# design.net
KiCad netlist of a schematic drawn in Altium Designer
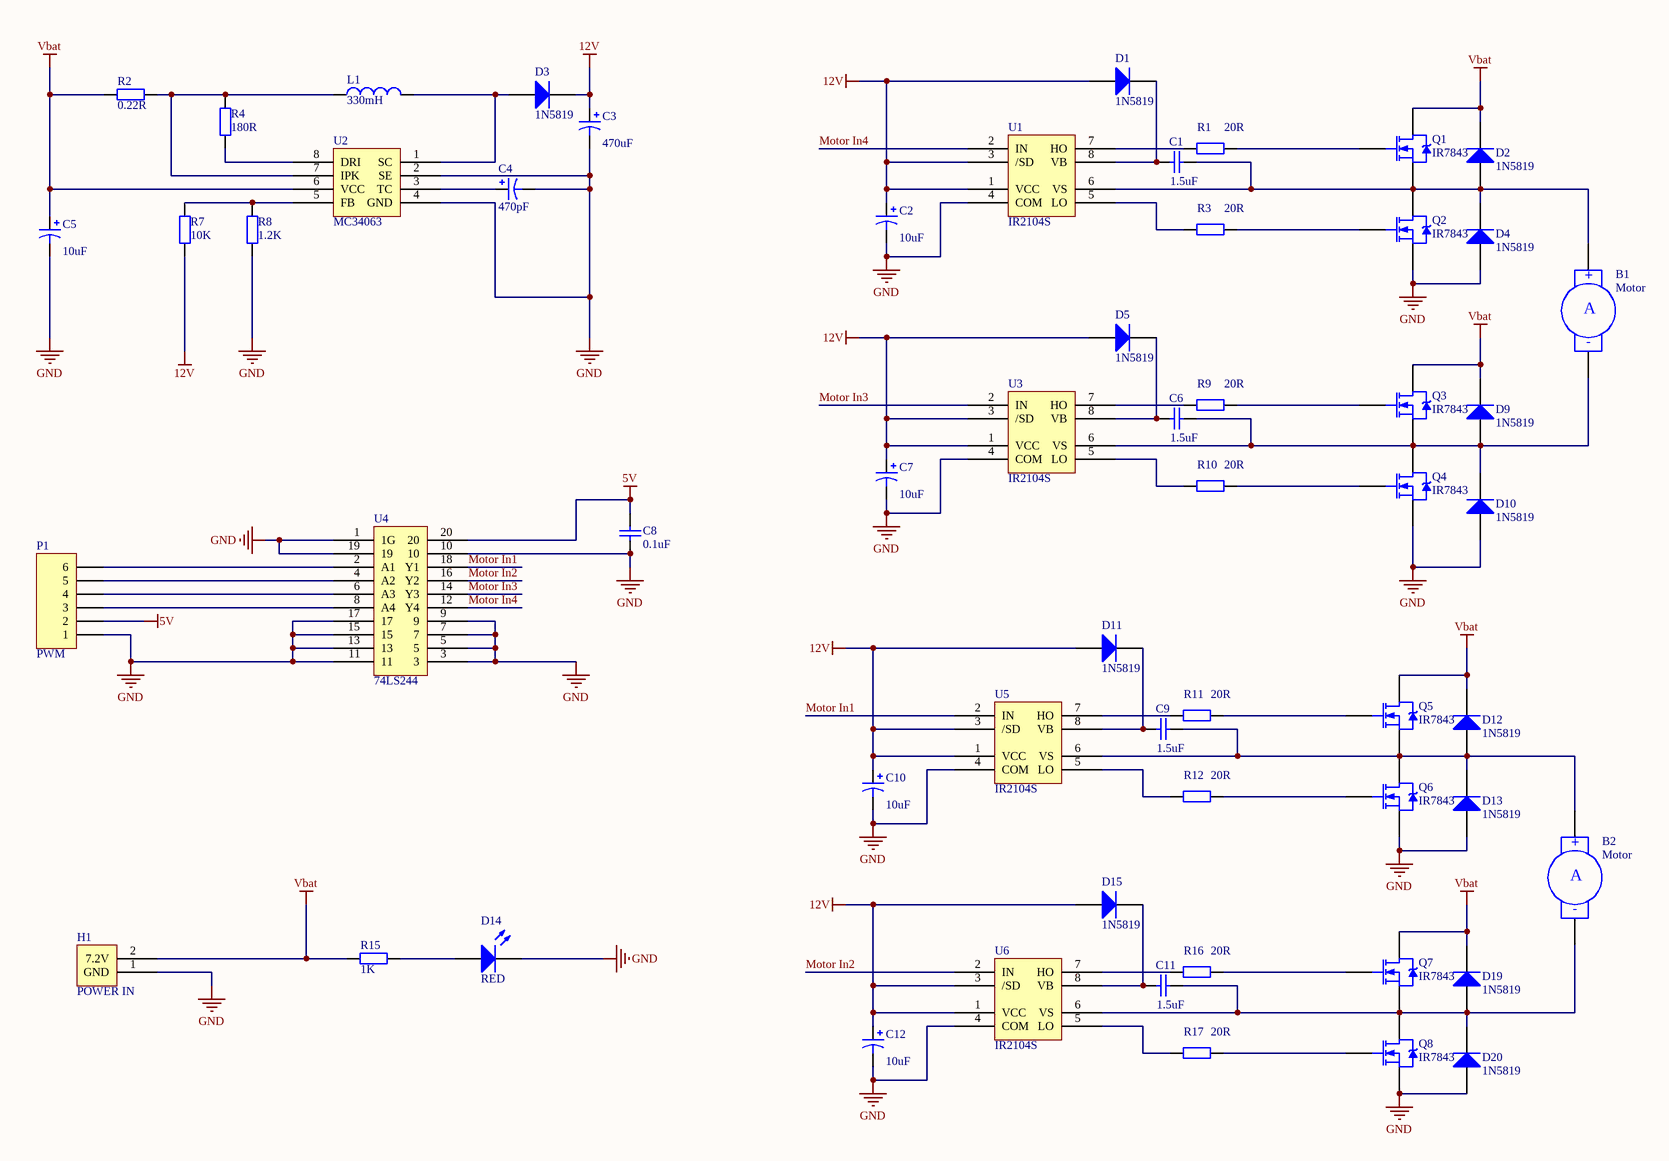
[diagram p0: 驱动原理图.SchDoc]

(export (version "E")
  (design (tool "Eeschema 10.0.6"))
  (components
    (comp (ref "B1")
      (value "Motor")
      (footprint "KF301-2P")
      (description "Servo Motor")
      (fields (field (name "PUBLISHER") "Altium Limited"))
      (libsource (lib "Miscellaneous Devices") (part "Motor Servo"))
    )
    (comp (ref "B2")
      (value "Motor")
      (footprint "KF301-2P")
      (description "Servo Motor")
      (fields (field (name "PUBLISHER") "Altium Limited"))
      (libsource (lib "Miscellaneous Devices") (part "Motor Servo"))
    )
    (comp (ref "C1")
      (value "1.5uF")
      (footprint "0805(2012)")
      (description "Capacitor")
      (fields (field (name "Comment") "Cap") (field (name "PUBLISHER") "Altium Limited"))
      (libsource (lib "Miscellaneous Devices") (part "Cap"))
    )
    (comp (ref "C2")
      (value "10uF")
      (footprint "SOD-323(0805)")
      (description "Polarized Capacitor (Radial)")
      (fields (field (name "Comment") "Cap Pol1") (field (name "PUBLISHER") "Altium Limited"))
      (libsource (lib "Miscellaneous Devices") (part "Cap Pol1"))
    )
    (comp (ref "C3")
      (value "470uF")
      (footprint "RB5-10.5")
      (description "Polarized Capacitor (Radial)")
      (fields (field (name "Comment") "Cap Pol1") (field (name "PUBLISHER") "Altium Limited"))
      (libsource (lib "Miscellaneous Devices") (part "Cap Pol1"))
    )
    (comp (ref "C4")
      (value "470pF")
      (footprint "SOD-323(0805)")
      (description "Polarized Capacitor (Radial)")
      (fields (field (name "Comment") "Cap Pol1") (field (name "PUBLISHER") "Altium Limited"))
      (libsource (lib "Miscellaneous Devices") (part "Cap Pol1"))
    )
    (comp (ref "C5")
      (value "10uF")
      (footprint "SOD-323(0805)")
      (description "Polarized Capacitor (Radial)")
      (fields (field (name "Comment") "Cap Pol1") (field (name "PUBLISHER") "Altium Limited"))
      (libsource (lib "Miscellaneous Devices") (part "Cap Pol1"))
    )
    (comp (ref "C6")
      (value "1.5uF")
      (footprint "0805(2012)")
      (description "Capacitor")
      (fields (field (name "Comment") "Cap") (field (name "PUBLISHER") "Altium Limited"))
      (libsource (lib "Miscellaneous Devices") (part "Cap"))
    )
    (comp (ref "C7")
      (value "10uF")
      (footprint "SOD-323(0805)")
      (description "Polarized Capacitor (Radial)")
      (fields (field (name "Comment") "Cap Pol1") (field (name "PUBLISHER") "Altium Limited"))
      (libsource (lib "Miscellaneous Devices") (part "Cap Pol1"))
    )
    (comp (ref "C8")
      (value "0.1uF")
      (footprint "0805(2012)")
      (description "Capacitor")
      (fields (field (name "Comment") "Cap") (field (name "PUBLISHER") "Altium Limited"))
      (libsource (lib "LY") (part "Cap"))
    )
    (comp (ref "C9")
      (value "1.5uF")
      (footprint "0805(2012)")
      (description "Capacitor")
      (fields (field (name "Comment") "Cap") (field (name "PUBLISHER") "Altium Limited"))
      (libsource (lib "Miscellaneous Devices") (part "Cap"))
    )
    (comp (ref "C10")
      (value "10uF")
      (footprint "SOD-323(0805)")
      (description "Polarized Capacitor (Radial)")
      (fields (field (name "Comment") "Cap Pol1") (field (name "PUBLISHER") "Altium Limited"))
      (libsource (lib "Miscellaneous Devices") (part "Cap Pol1"))
    )
    (comp (ref "C11")
      (value "1.5uF")
      (footprint "0805(2012)")
      (description "Capacitor")
      (fields (field (name "Comment") "Cap") (field (name "PUBLISHER") "Altium Limited"))
      (libsource (lib "Miscellaneous Devices") (part "Cap"))
    )
    (comp (ref "C12")
      (value "10uF")
      (footprint "SOD-323(0805)")
      (description "Polarized Capacitor (Radial)")
      (fields (field (name "Comment") "Cap Pol1") (field (name "PUBLISHER") "Altium Limited"))
      (libsource (lib "Miscellaneous Devices") (part "Cap Pol1"))
    )
    (comp (ref "D1")
      (value "1N5819")
      (footprint "0805(2012)")
      (description "Silicon Epitaxial Planar Diode for Various Detector, Modulator, Demodulator")
      (fields (field (name "PUBLISHER") "Altium Limited"))
      (libsource (lib "Renesas Diode") (part "1N4148"))
    )
    (comp (ref "D2")
      (value "1N5819")
      (footprint "0805(2012)")
      (description "Silicon Epitaxial Planar Diode for Various Detector, Modulator, Demodulator")
      (fields (field (name "PUBLISHER") "Altium Limited"))
      (libsource (lib "Renesas Diode") (part "1N4148"))
    )
    (comp (ref "D3")
      (value "1N5819")
      (footprint "0805(2012)")
      (description "Silicon Epitaxial Planar Diode for Various Detector, Modulator, Demodulator")
      (fields (field (name "PUBLISHER") "Altium Limited"))
      (libsource (lib "Renesas Diode") (part "1N4148"))
    )
    (comp (ref "D4")
      (value "1N5819")
      (footprint "0805(2012)")
      (description "Silicon Epitaxial Planar Diode for Various Detector, Modulator, Demodulator")
      (fields (field (name "PUBLISHER") "Altium Limited"))
      (libsource (lib "Renesas Diode") (part "1N4148"))
    )
    (comp (ref "D5")
      (value "1N5819")
      (footprint "0805(2012)")
      (description "Silicon Epitaxial Planar Diode for Various Detector, Modulator, Demodulator")
      (fields (field (name "PUBLISHER") "Altium Limited"))
      (libsource (lib "Renesas Diode") (part "1N4148"))
    )
    (comp (ref "D9")
      (value "1N5819")
      (footprint "0805(2012)")
      (description "Silicon Epitaxial Planar Diode for Various Detector, Modulator, Demodulator")
      (fields (field (name "PUBLISHER") "Altium Limited"))
      (libsource (lib "Renesas Diode") (part "1N4148"))
    )
    (comp (ref "D10")
      (value "1N5819")
      (footprint "0805(2012)")
      (description "Silicon Epitaxial Planar Diode for Various Detector, Modulator, Demodulator")
      (fields (field (name "PUBLISHER") "Altium Limited"))
      (libsource (lib "Renesas Diode") (part "1N4148"))
    )
    (comp (ref "D11")
      (value "1N5819")
      (footprint "0805(2012)")
      (description "Silicon Epitaxial Planar Diode for Various Detector, Modulator, Demodulator")
      (fields (field (name "PUBLISHER") "Altium Limited"))
      (libsource (lib "Renesas Diode") (part "1N4148"))
    )
    (comp (ref "D12")
      (value "1N5819")
      (footprint "0805(2012)")
      (description "Silicon Epitaxial Planar Diode for Various Detector, Modulator, Demodulator")
      (fields (field (name "PUBLISHER") "Altium Limited"))
      (libsource (lib "Renesas Diode") (part "1N4148"))
    )
    (comp (ref "D13")
      (value "1N5819")
      (footprint "0805(2012)")
      (description "Silicon Epitaxial Planar Diode for Various Detector, Modulator, Demodulator")
      (fields (field (name "PUBLISHER") "Altium Limited"))
      (libsource (lib "Renesas Diode") (part "1N4148"))
    )
    (comp (ref "D14")
      (value "RED")
      (footprint "0805LED")
      (description "Typical RED, GREEN, YELLOW, AMBER GaAs LED")
      (fields (field (name "PUBLISHER") "Altium Limited"))
      (libsource (lib "LY") (part "LED2"))
    )
    (comp (ref "D15")
      (value "1N5819")
      (footprint "0805(2012)")
      (description "Silicon Epitaxial Planar Diode for Various Detector, Modulator, Demodulator")
      (fields (field (name "PUBLISHER") "Altium Limited"))
      (libsource (lib "Renesas Diode") (part "1N4148"))
    )
    (comp (ref "D19")
      (value "1N5819")
      (footprint "0805(2012)")
      (description "Silicon Epitaxial Planar Diode for Various Detector, Modulator, Demodulator")
      (fields (field (name "PUBLISHER") "Altium Limited"))
      (libsource (lib "Renesas Diode") (part "1N4148"))
    )
    (comp (ref "D20")
      (value "1N5819")
      (footprint "0805(2012)")
      (description "Silicon Epitaxial Planar Diode for Various Detector, Modulator, Demodulator")
      (fields (field (name "PUBLISHER") "Altium Limited"))
      (libsource (lib "Renesas Diode") (part "1N4148"))
    )
    (comp (ref "H1")
      (value "POWER IN")
      (footprint "KF301-2P")
      (libsource (lib "MOS motor") (part "POWER IN"))
    )
    (comp (ref "L1")
      (value "330mH")
      (footprint "电感10*12")
      (description "Inductor")
      (fields (field (name "PUBLISHER") "Altium Limited"))
      (libsource (lib "Miscellaneous Devices") (part "Inductor"))
    )
    (comp (ref "P1")
      (value "PWM")
      (footprint "HDR1X6")
      (description "Header, 6-Pin")
      (fields (field (name "PUBLISHER") "Altium Limited"))
      (libsource (lib "Miscellaneous Connectors") (part "Header 6"))
    )
    (comp (ref "Q1")
      (value "IR7843")
      (footprint "LR7843")
      (description "N-Channel Power MOSFET")
      (fields (field (name "PUBLISHER") "Altium Limited"))
      (libsource (lib "PowerIn") (part "IR7843"))
    )
    (comp (ref "Q2")
      (value "IR7843")
      (footprint "LR7843")
      (description "N-Channel Power MOSFET")
      (fields (field (name "PUBLISHER") "Altium Limited"))
      (libsource (lib "PowerIn") (part "IR7843"))
    )
    (comp (ref "Q3")
      (value "IR7843")
      (footprint "LR7843")
      (description "N-Channel Power MOSFET")
      (fields (field (name "PUBLISHER") "Altium Limited"))
      (libsource (lib "PowerIn") (part "IR7843"))
    )
    (comp (ref "Q4")
      (value "IR7843")
      (footprint "LR7843")
      (description "N-Channel Power MOSFET")
      (fields (field (name "PUBLISHER") "Altium Limited"))
      (libsource (lib "PowerIn") (part "IR7843"))
    )
    (comp (ref "Q5")
      (value "IR7843")
      (footprint "LR7843")
      (description "N-Channel Power MOSFET")
      (fields (field (name "PUBLISHER") "Altium Limited"))
      (libsource (lib "PowerIn") (part "IR7843"))
    )
    (comp (ref "Q6")
      (value "IR7843")
      (footprint "LR7843")
      (description "N-Channel Power MOSFET")
      (fields (field (name "PUBLISHER") "Altium Limited"))
      (libsource (lib "PowerIn") (part "IR7843"))
    )
    (comp (ref "Q7")
      (value "IR7843")
      (footprint "LR7843")
      (description "N-Channel Power MOSFET")
      (fields (field (name "PUBLISHER") "Altium Limited"))
      (libsource (lib "PowerIn") (part "IR7843"))
    )
    (comp (ref "Q8")
      (value "IR7843")
      (footprint "LR7843")
      (description "N-Channel Power MOSFET")
      (fields (field (name "PUBLISHER") "Altium Limited"))
      (libsource (lib "PowerIn") (part "IR7843"))
    )
    (comp (ref "R1")
      (value "20R")
      (footprint "0805(2012)")
      (description "Resistor")
      (fields (field (name "Comment") "Res2") (field (name "PUBLISHER") "Altium Limited"))
      (libsource (lib "altium-import") (part "root_0_Res2_"))
    )
    (comp (ref "R2")
      (value "0.22R")
      (footprint "1206(3216)")
      (description "Resistor")
      (fields (field (name "Comment") "Res2") (field (name "PUBLISHER") "Altium Limited"))
      (libsource (lib "altium-import") (part "root_2_Res2_"))
    )
    (comp (ref "R3")
      (value "20R")
      (footprint "0805(2012)")
      (description "Resistor")
      (fields (field (name "Comment") "Res2") (field (name "PUBLISHER") "Altium Limited"))
      (libsource (lib "altium-import") (part "root_0_Res2_"))
    )
    (comp (ref "R4")
      (value "180R")
      (footprint "0805(2012)")
      (description "Resistor")
      (fields (field (name "Comment") "Res2") (field (name "PUBLISHER") "Altium Limited"))
      (libsource (lib "LY") (part "Res2"))
    )
    (comp (ref "R7")
      (value "10K")
      (footprint "0805(2012)")
      (description "Resistor")
      (fields (field (name "Comment") "Res2") (field (name "PUBLISHER") "Altium Limited"))
      (libsource (lib "LY") (part "Res2"))
    )
    (comp (ref "R8")
      (value "1.2K")
      (footprint "0805(2012)")
      (description "Resistor")
      (fields (field (name "Comment") "Res2") (field (name "PUBLISHER") "Altium Limited"))
      (libsource (lib "LY") (part "Res2"))
    )
    (comp (ref "R9")
      (value "20R")
      (footprint "0805(2012)")
      (description "Resistor")
      (fields (field (name "Comment") "Res2") (field (name "PUBLISHER") "Altium Limited"))
      (libsource (lib "altium-import") (part "root_0_Res2_"))
    )
    (comp (ref "R10")
      (value "20R")
      (footprint "0805(2012)")
      (description "Resistor")
      (fields (field (name "Comment") "Res2") (field (name "PUBLISHER") "Altium Limited"))
      (libsource (lib "altium-import") (part "root_0_Res2_"))
    )
    (comp (ref "R11")
      (value "20R")
      (footprint "0805(2012)")
      (description "Resistor")
      (fields (field (name "Comment") "Res2") (field (name "PUBLISHER") "Altium Limited"))
      (libsource (lib "altium-import") (part "root_0_Res2_"))
    )
    (comp (ref "R12")
      (value "20R")
      (footprint "0805(2012)")
      (description "Resistor")
      (fields (field (name "Comment") "Res2") (field (name "PUBLISHER") "Altium Limited"))
      (libsource (lib "altium-import") (part "root_0_Res2_"))
    )
    (comp (ref "R15")
      (value "1K")
      (footprint "0805(2012)")
      (description "Resistor")
      (fields (field (name "Comment") "Res2") (field (name "PUBLISHER") "Altium Limited"))
      (libsource (lib "") (part "Res2_1"))
    )
    (comp (ref "R16")
      (value "20R")
      (footprint "0805(2012)")
      (description "Resistor")
      (fields (field (name "Comment") "Res2") (field (name "PUBLISHER") "Altium Limited"))
      (libsource (lib "altium-import") (part "root_0_Res2_"))
    )
    (comp (ref "R17")
      (value "20R")
      (footprint "0805(2012)")
      (description "Resistor")
      (fields (field (name "Comment") "Res2") (field (name "PUBLISHER") "Altium Limited"))
      (libsource (lib "altium-import") (part "root_0_Res2_"))
    )
    (comp (ref "U1") (value "IR2104S") (footprint "IR2104S") (libsource (lib "LY") (part "IR2104S")))
    (comp (ref "U2") (value "MC34063") (footprint "MC34063") (libsource (lib "LY") (part "MC34063")))
    (comp (ref "U3") (value "IR2104S") (footprint "IR2104S") (libsource (lib "LY") (part "IR2104S")))
    (comp (ref "U4") (value "74LS244") (footprint "74ls244DA") (libsource (lib "LY") (part "74LS244")))
    (comp (ref "U5") (value "IR2104S") (footprint "IR2104S") (libsource (lib "LY") (part "IR2104S")))
    (comp (ref "U6") (value "IR2104S") (footprint "IR2104S") (libsource (lib "LY") (part "IR2104S")))
  )
  (nets
    (net (code "1") (name "/Motor In1") (class "Default")
      (node (ref "U4") (pin "18") (pinfunction "Y1_18") (pintype "passive"))
      (node (ref "U5") (pin "2") (pinfunction "IN_2") (pintype "passive"))
    )
    (net (code "2") (name "/Motor In2") (class "Default")
      (node (ref "U4") (pin "16") (pinfunction "Y2_16") (pintype "passive"))
      (node (ref "U6") (pin "2") (pinfunction "IN_2") (pintype "passive"))
    )
    (net (code "3") (name "/Motor In3") (class "Default")
      (node (ref "U3") (pin "2") (pinfunction "IN_2") (pintype "passive"))
      (node (ref "U4") (pin "14") (pinfunction "Y3_14") (pintype "passive"))
    )
    (net (code "4") (name "/Motor In4") (class "Default")
      (node (ref "U1") (pin "2") (pinfunction "IN_2") (pintype "passive"))
      (node (ref "U4") (pin "12") (pinfunction "Y4_12") (pintype "passive"))
    )
    (net (code "5") (name "5V") (class "Default")
      (node (ref "C8") (pin "2") (pinfunction "2_2") (pintype "passive"))
      (node (ref "P1") (pin "2") (pinfunction "2_2") (pintype "passive"))
      (node (ref "U4") (pin "20") (pinfunction "20_20") (pintype "passive"))
    )
    (net (code "6") (name "12V") (class "Default")
      (node (ref "C10") (pin "1") (pinfunction "1_1") (pintype "passive"))
      (node (ref "C12") (pin "1") (pinfunction "1_1") (pintype "passive"))
      (node (ref "C2") (pin "1") (pinfunction "1_1") (pintype "passive"))
      (node (ref "C3") (pin "1") (pinfunction "1_1") (pintype "passive"))
      (node (ref "C7") (pin "1") (pinfunction "1_1") (pintype "passive"))
      (node (ref "D1") (pin "2") (pinfunction "A_2") (pintype "passive"))
      (node (ref "D11") (pin "2") (pinfunction "A_2") (pintype "passive"))
      (node (ref "D15") (pin "2") (pinfunction "A_2") (pintype "passive"))
      (node (ref "D3") (pin "1") (pinfunction "K_1") (pintype "passive"))
      (node (ref "D5") (pin "2") (pinfunction "A_2") (pintype "passive"))
      (node (ref "R7") (pin "1") (pinfunction "1_1") (pintype "passive"))
      (node (ref "U1") (pin "1") (pinfunction "VCC_1") (pintype "passive"))
      (node (ref "U1") (pin "3") (pinfunction "/SD_3") (pintype "passive"))
      (node (ref "U3") (pin "1") (pinfunction "VCC_1") (pintype "passive"))
      (node (ref "U3") (pin "3") (pinfunction "/SD_3") (pintype "passive"))
      (node (ref "U5") (pin "1") (pinfunction "VCC_1") (pintype "passive"))
      (node (ref "U5") (pin "3") (pinfunction "/SD_3") (pintype "passive"))
      (node (ref "U6") (pin "1") (pinfunction "VCC_1") (pintype "passive"))
      (node (ref "U6") (pin "3") (pinfunction "/SD_3") (pintype "passive"))
    )
    (net (code "7") (name "GND") (class "Default")
      (node (ref "C10") (pin "2") (pinfunction "2_2") (pintype "passive"))
      (node (ref "C12") (pin "2") (pinfunction "2_2") (pintype "passive"))
      (node (ref "C2") (pin "2") (pinfunction "2_2") (pintype "passive"))
      (node (ref "C3") (pin "2") (pinfunction "2_2") (pintype "passive"))
      (node (ref "C4") (pin "2") (pinfunction "2_2") (pintype "passive"))
      (node (ref "C5") (pin "2") (pinfunction "2_2") (pintype "passive"))
      (node (ref "C7") (pin "2") (pinfunction "2_2") (pintype "passive"))
      (node (ref "C8") (pin "1") (pinfunction "1_1") (pintype "passive"))
      (node (ref "D10") (pin "2") (pinfunction "A_2") (pintype "passive"))
      (node (ref "D13") (pin "2") (pinfunction "A_2") (pintype "passive"))
      (node (ref "D14") (pin "2") (pinfunction "K_2") (pintype "passive"))
      (node (ref "D20") (pin "2") (pinfunction "A_2") (pintype "passive"))
      (node (ref "D4") (pin "2") (pinfunction "A_2") (pintype "passive"))
      (node (ref "H1") (pin "1") (pinfunction "GND_1") (pintype "passive"))
      (node (ref "P1") (pin "1") (pinfunction "1_1") (pintype "passive"))
      (node (ref "Q2") (pin "3") (pinfunction "S_3") (pintype "passive"))
      (node (ref "Q4") (pin "3") (pinfunction "S_3") (pintype "passive"))
      (node (ref "Q6") (pin "3") (pinfunction "S_3") (pintype "passive"))
      (node (ref "Q8") (pin "3") (pinfunction "S_3") (pintype "passive"))
      (node (ref "R8") (pin "1") (pinfunction "1_1") (pintype "passive"))
      (node (ref "U1") (pin "4") (pinfunction "COM_4") (pintype "passive"))
      (node (ref "U2") (pin "2") (pinfunction "SE_2") (pintype "passive"))
      (node (ref "U2") (pin "4") (pinfunction "GND_4") (pintype "passive"))
      (node (ref "U3") (pin "4") (pinfunction "COM_4") (pintype "passive"))
      (node (ref "U4") (pin "1") (pinfunction "1G_1") (pintype "passive"))
      (node (ref "U4") (pin "10") (pinfunction "10_10") (pintype "passive"))
      (node (ref "U4") (pin "11") (pinfunction "11_11") (pintype "passive"))
      (node (ref "U4") (pin "13") (pinfunction "13_13") (pintype "passive"))
      (node (ref "U4") (pin "15") (pinfunction "15_15") (pintype "passive"))
      (node (ref "U4") (pin "17") (pinfunction "17_17") (pintype "passive"))
      (node (ref "U4") (pin "19") (pinfunction "19_19") (pintype "passive"))
      (node (ref "U4") (pin "3") (pinfunction "3_3") (pintype "passive"))
      (node (ref "U4") (pin "5") (pinfunction "5_5") (pintype "passive"))
      (node (ref "U4") (pin "7") (pinfunction "7_7") (pintype "passive"))
      (node (ref "U4") (pin "9") (pinfunction "9_9") (pintype "passive"))
      (node (ref "U5") (pin "4") (pinfunction "COM_4") (pintype "passive"))
      (node (ref "U6") (pin "4") (pinfunction "COM_4") (pintype "passive"))
    )
    (net (code "8") (name "Net-(B1-+)") (class "Default")
      (node (ref "B1") (pin "1") (pinfunction "+_1") (pintype "passive"))
      (node (ref "C1") (pin "2") (pinfunction "2_2") (pintype "passive"))
      (node (ref "D2") (pin "2") (pinfunction "A_2") (pintype "passive"))
      (node (ref "D4") (pin "1") (pinfunction "K_1") (pintype "passive"))
      (node (ref "Q1") (pin "3") (pinfunction "S_3") (pintype "passive"))
      (node (ref "Q2") (pin "2") (pinfunction "D_2") (pintype "passive"))
      (node (ref "U1") (pin "6") (pinfunction "VS_6") (pintype "passive"))
    )
    (net (code "9") (name "Net-(B1--)") (class "Default")
      (node (ref "B1") (pin "2") (pinfunction "-_2") (pintype "passive"))
      (node (ref "C6") (pin "2") (pinfunction "2_2") (pintype "passive"))
      (node (ref "D10") (pin "1") (pinfunction "K_1") (pintype "passive"))
      (node (ref "D9") (pin "2") (pinfunction "A_2") (pintype "passive"))
      (node (ref "Q3") (pin "3") (pinfunction "S_3") (pintype "passive"))
      (node (ref "Q4") (pin "2") (pinfunction "D_2") (pintype "passive"))
      (node (ref "U3") (pin "6") (pinfunction "VS_6") (pintype "passive"))
    )
    (net (code "10") (name "Net-(B2-+)") (class "Default")
      (node (ref "B2") (pin "1") (pinfunction "+_1") (pintype "passive"))
      (node (ref "C9") (pin "2") (pinfunction "2_2") (pintype "passive"))
      (node (ref "D12") (pin "2") (pinfunction "A_2") (pintype "passive"))
      (node (ref "D13") (pin "1") (pinfunction "K_1") (pintype "passive"))
      (node (ref "Q5") (pin "3") (pinfunction "S_3") (pintype "passive"))
      (node (ref "Q6") (pin "2") (pinfunction "D_2") (pintype "passive"))
      (node (ref "U5") (pin "6") (pinfunction "VS_6") (pintype "passive"))
    )
    (net (code "11") (name "Net-(B2--)") (class "Default")
      (node (ref "B2") (pin "2") (pinfunction "-_2") (pintype "passive"))
      (node (ref "C11") (pin "2") (pinfunction "2_2") (pintype "passive"))
      (node (ref "D19") (pin "2") (pinfunction "A_2") (pintype "passive"))
      (node (ref "D20") (pin "1") (pinfunction "K_1") (pintype "passive"))
      (node (ref "Q7") (pin "3") (pinfunction "S_3") (pintype "passive"))
      (node (ref "Q8") (pin "2") (pinfunction "D_2") (pintype "passive"))
      (node (ref "U6") (pin "6") (pinfunction "VS_6") (pintype "passive"))
    )
    (net (code "12") (name "Net-(D1-K)") (class "Default")
      (node (ref "C1") (pin "1") (pinfunction "1_1") (pintype "passive"))
      (node (ref "D1") (pin "1") (pinfunction "K_1") (pintype "passive"))
      (node (ref "U1") (pin "8") (pinfunction "VB_8") (pintype "passive"))
    )
    (net (code "13") (name "Net-(D3-A)") (class "Default")
      (node (ref "D3") (pin "2") (pinfunction "A_2") (pintype "passive"))
      (node (ref "L1") (pin "2") (pinfunction "2_2") (pintype "passive"))
      (node (ref "U2") (pin "1") (pinfunction "SC_1") (pintype "passive"))
    )
    (net (code "14") (name "Net-(D5-K)") (class "Default")
      (node (ref "C6") (pin "1") (pinfunction "1_1") (pintype "passive"))
      (node (ref "D5") (pin "1") (pinfunction "K_1") (pintype "passive"))
      (node (ref "U3") (pin "8") (pinfunction "VB_8") (pintype "passive"))
    )
    (net (code "15") (name "Net-(D11-K)") (class "Default")
      (node (ref "C9") (pin "1") (pinfunction "1_1") (pintype "passive"))
      (node (ref "D11") (pin "1") (pinfunction "K_1") (pintype "passive"))
      (node (ref "U5") (pin "8") (pinfunction "VB_8") (pintype "passive"))
    )
    (net (code "16") (name "Net-(D14-A)") (class "Default")
      (node (ref "D14") (pin "1") (pinfunction "A_1") (pintype "passive"))
      (node (ref "R15") (pin "2") (pinfunction "2_2") (pintype "passive"))
    )
    (net (code "17") (name "Net-(D15-K)") (class "Default")
      (node (ref "C11") (pin "1") (pinfunction "1_1") (pintype "passive"))
      (node (ref "D15") (pin "1") (pinfunction "K_1") (pintype "passive"))
      (node (ref "U6") (pin "8") (pinfunction "VB_8") (pintype "passive"))
    )
    (net (code "18") (name "Net-(Q1-G)") (class "Default")
      (node (ref "Q1") (pin "1") (pinfunction "G_1") (pintype "passive"))
      (node (ref "R1") (pin "2") (pinfunction "2_2") (pintype "passive"))
    )
    (net (code "19") (name "Net-(Q2-G)") (class "Default")
      (node (ref "Q2") (pin "1") (pinfunction "G_1") (pintype "passive"))
      (node (ref "R3") (pin "2") (pinfunction "2_2") (pintype "passive"))
    )
    (net (code "20") (name "Net-(Q3-G)") (class "Default")
      (node (ref "Q3") (pin "1") (pinfunction "G_1") (pintype "passive"))
      (node (ref "R9") (pin "2") (pinfunction "2_2") (pintype "passive"))
    )
    (net (code "21") (name "Net-(Q4-G)") (class "Default")
      (node (ref "Q4") (pin "1") (pinfunction "G_1") (pintype "passive"))
      (node (ref "R10") (pin "2") (pinfunction "2_2") (pintype "passive"))
    )
    (net (code "22") (name "Net-(Q5-G)") (class "Default")
      (node (ref "Q5") (pin "1") (pinfunction "G_1") (pintype "passive"))
      (node (ref "R11") (pin "2") (pinfunction "2_2") (pintype "passive"))
    )
    (net (code "23") (name "Net-(Q6-G)") (class "Default")
      (node (ref "Q6") (pin "1") (pinfunction "G_1") (pintype "passive"))
      (node (ref "R12") (pin "2") (pinfunction "2_2") (pintype "passive"))
    )
    (net (code "24") (name "Net-(Q7-G)") (class "Default")
      (node (ref "Q7") (pin "1") (pinfunction "G_1") (pintype "passive"))
      (node (ref "R16") (pin "2") (pinfunction "2_2") (pintype "passive"))
    )
    (net (code "25") (name "Net-(Q8-G)") (class "Default")
      (node (ref "Q8") (pin "1") (pinfunction "G_1") (pintype "passive"))
      (node (ref "R17") (pin "2") (pinfunction "2_2") (pintype "passive"))
    )
    (net (code "26") (name "Net-(U1-HO)") (class "Default")
      (node (ref "R1") (pin "1") (pinfunction "1_1") (pintype "passive"))
      (node (ref "U1") (pin "7") (pinfunction "HO_7") (pintype "passive"))
    )
    (net (code "27") (name "Net-(U1-LO)") (class "Default")
      (node (ref "R3") (pin "1") (pinfunction "1_1") (pintype "passive"))
      (node (ref "U1") (pin "5") (pinfunction "LO_5") (pintype "passive"))
    )
    (net (code "28") (name "Net-(U2-DRI)") (class "Default")
      (node (ref "R4") (pin "1") (pinfunction "1_1") (pintype "passive"))
      (node (ref "U2") (pin "8") (pinfunction "DRI_8") (pintype "passive"))
    )
    (net (code "29") (name "Net-(U2-FB)") (class "Default")
      (node (ref "R7") (pin "2") (pinfunction "2_2") (pintype "passive"))
      (node (ref "R8") (pin "2") (pinfunction "2_2") (pintype "passive"))
      (node (ref "U2") (pin "5") (pinfunction "FB_5") (pintype "passive"))
    )
    (net (code "30") (name "Net-(U2-IPK)") (class "Default")
      (node (ref "L1") (pin "1") (pinfunction "1_1") (pintype "passive"))
      (node (ref "R2") (pin "1") (pinfunction "1_1") (pintype "passive"))
      (node (ref "R4") (pin "2") (pinfunction "2_2") (pintype "passive"))
      (node (ref "U2") (pin "7") (pinfunction "IPK_7") (pintype "passive"))
    )
    (net (code "31") (name "Net-(U2-TC)") (class "Default")
      (node (ref "C4") (pin "1") (pinfunction "1_1") (pintype "passive"))
      (node (ref "U2") (pin "3") (pinfunction "TC_3") (pintype "passive"))
    )
    (net (code "32") (name "Net-(U3-HO)") (class "Default")
      (node (ref "R9") (pin "1") (pinfunction "1_1") (pintype "passive"))
      (node (ref "U3") (pin "7") (pinfunction "HO_7") (pintype "passive"))
    )
    (net (code "33") (name "Net-(U3-LO)") (class "Default")
      (node (ref "R10") (pin "1") (pinfunction "1_1") (pintype "passive"))
      (node (ref "U3") (pin "5") (pinfunction "LO_5") (pintype "passive"))
    )
    (net (code "34") (name "Net-(U4-A1)") (class "Default")
      (node (ref "P1") (pin "6") (pinfunction "6_6") (pintype "passive"))
      (node (ref "U4") (pin "2") (pinfunction "A1_2") (pintype "passive"))
    )
    (net (code "35") (name "Net-(U4-A2)") (class "Default")
      (node (ref "P1") (pin "5") (pinfunction "5_5") (pintype "passive"))
      (node (ref "U4") (pin "4") (pinfunction "A2_4") (pintype "passive"))
    )
    (net (code "36") (name "Net-(U4-A3)") (class "Default")
      (node (ref "P1") (pin "4") (pinfunction "4_4") (pintype "passive"))
      (node (ref "U4") (pin "6") (pinfunction "A3_6") (pintype "passive"))
    )
    (net (code "37") (name "Net-(U4-A4)") (class "Default")
      (node (ref "P1") (pin "3") (pinfunction "3_3") (pintype "passive"))
      (node (ref "U4") (pin "8") (pinfunction "A4_8") (pintype "passive"))
    )
    (net (code "38") (name "Net-(U5-HO)") (class "Default")
      (node (ref "R11") (pin "1") (pinfunction "1_1") (pintype "passive"))
      (node (ref "U5") (pin "7") (pinfunction "HO_7") (pintype "passive"))
    )
    (net (code "39") (name "Net-(U5-LO)") (class "Default")
      (node (ref "R12") (pin "1") (pinfunction "1_1") (pintype "passive"))
      (node (ref "U5") (pin "5") (pinfunction "LO_5") (pintype "passive"))
    )
    (net (code "40") (name "Net-(U6-HO)") (class "Default")
      (node (ref "R16") (pin "1") (pinfunction "1_1") (pintype "passive"))
      (node (ref "U6") (pin "7") (pinfunction "HO_7") (pintype "passive"))
    )
    (net (code "41") (name "Net-(U6-LO)") (class "Default")
      (node (ref "R17") (pin "1") (pinfunction "1_1") (pintype "passive"))
      (node (ref "U6") (pin "5") (pinfunction "LO_5") (pintype "passive"))
    )
    (net (code "42") (name "Vbat") (class "Default")
      (node (ref "C5") (pin "1") (pinfunction "1_1") (pintype "passive"))
      (node (ref "D12") (pin "1") (pinfunction "K_1") (pintype "passive"))
      (node (ref "D19") (pin "1") (pinfunction "K_1") (pintype "passive"))
      (node (ref "D2") (pin "1") (pinfunction "K_1") (pintype "passive"))
      (node (ref "D9") (pin "1") (pinfunction "K_1") (pintype "passive"))
      (node (ref "H1") (pin "2") (pinfunction "7.2V_2") (pintype "passive"))
      (node (ref "Q1") (pin "2") (pinfunction "D_2") (pintype "passive"))
      (node (ref "Q3") (pin "2") (pinfunction "D_2") (pintype "passive"))
      (node (ref "Q5") (pin "2") (pinfunction "D_2") (pintype "passive"))
      (node (ref "Q7") (pin "2") (pinfunction "D_2") (pintype "passive"))
      (node (ref "R15") (pin "1") (pinfunction "1_1") (pintype "passive"))
      (node (ref "R2") (pin "2") (pinfunction "2_2") (pintype "passive"))
      (node (ref "U2") (pin "6") (pinfunction "VCC_6") (pintype "passive"))
    )
  )
)
